# DT_AZP1524B1_SCH1_SHEET2__00A.net
KiCad netlist of a schematic drawn in Altium Designer
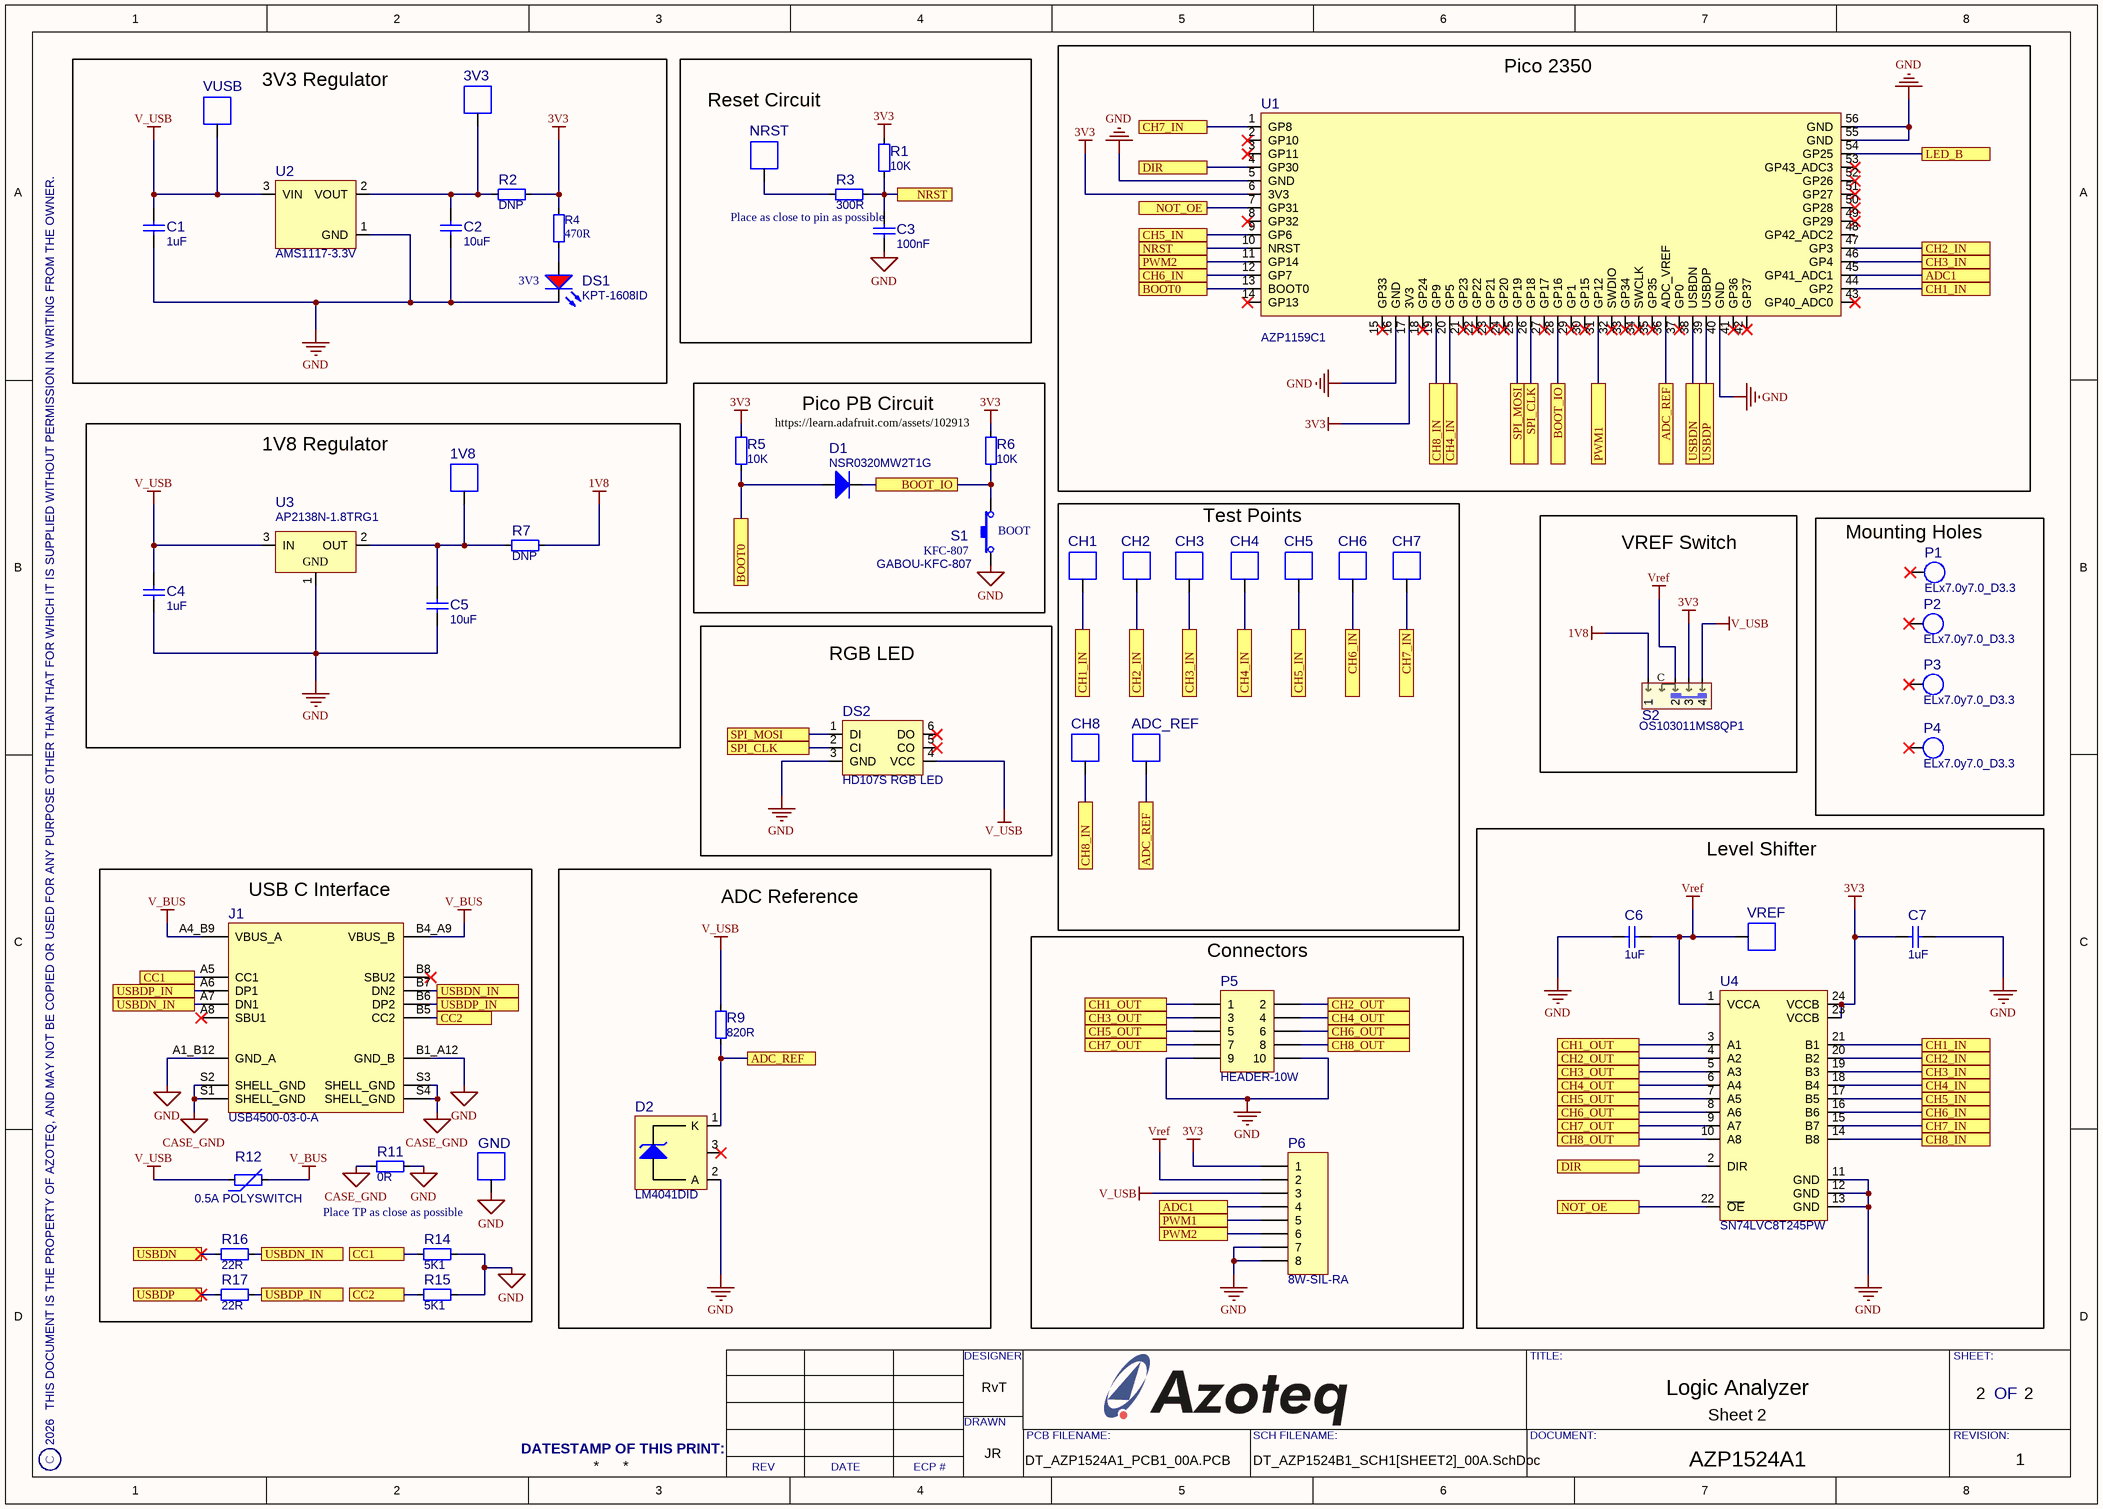
[diagram p0: DT_AZP1524B1_SCH1[SHEET2]_00A.SchDoc]

(export (version "E")
  (design (tool "Eeschema 10.0.6"))
  (components
    (comp (ref "1V8")
      (value "~")
      (footprint "TEST-POINT-1.5MM")
      (fields (field (name "CHECKED_BY") "*"))
      (libsource (lib "Miscellaneous") (part "TEST-POINT-SMD-1.5MM"))
    )
    (comp (ref "3V3")
      (value "~")
      (footprint "TEST-POINT-1.5MM")
      (fields (field (name "CHECKED_BY") "*"))
      (libsource (lib "Miscellaneous") (part "TEST-POINT-SMD-1.5MM"))
    )
    (comp (ref "ADC_REF")
      (value "~")
      (footprint "TEST-POINT-1.5MM")
      (fields (field (name "CHECKED_BY") "*"))
      (libsource (lib "Miscellaneous") (part "TEST-POINT-SMD-1.5MM"))
    )
    (comp (ref "C1")
      (value "1uF")
      (footprint "C-0603")
      (description "Capacitor, Ceramic, 1uF, 0603, X5R, 10%, 10V")
      (fields
        (field (name "INT_PART_NUMBER") "CAP0021")
        (field (name "MANUFACTURER") "Samsung")
        (field (name "CHECKED_BY") "Jason Reinecke")
      )
      (libsource (lib "Passive") (part "CAP 1u0F 0603 CER X5R 10% 10V"))
    )
    (comp (ref "C2")
      (value "10uF")
      (footprint "C-0603")
      (description "Capacitor, Ceramic, 10uF, 0603, X5R, 20%, 6V3 SAMSUNG")
      (fields
        (field (name "INT_PART_NUMBER") "CAP0076")
        (field (name "MANUFACTURER") "SAMSUNG")
        (field (name "CHECKED_BY") "Jason Reinecke")
      )
      (libsource (lib "Passive") (part "CAP 10uF 0603 CER X5R 20% 6V3 SAMSUNG"))
    )
    (comp (ref "C3")
      (value "100nF")
      (footprint "C-0603")
      (description "Capacitor, Ceramic, 100nF, 0603, X7R, 10%, 50V")
      (fields
        (field (name "INT_PART_NUMBER") "CAP0032")
        (field (name "MANUFACTURER") "Samsung")
        (field (name "CHECKED_BY") "Jason Reinecke")
      )
      (libsource (lib "Passive") (part "CAP 100nF 0603 CER X7R 10% 50V"))
    )
    (comp (ref "C4")
      (value "1uF")
      (footprint "C-0603")
      (description "Capacitor, Ceramic, 1uF, 0603, X5R, 10%, 10V")
      (fields
        (field (name "INT_PART_NUMBER") "CAP0021")
        (field (name "MANUFACTURER") "Samsung")
        (field (name "CHECKED_BY") "Jason Reinecke")
      )
      (libsource (lib "Passive") (part "CAP 1u0F 0603 CER X5R 10% 10V"))
    )
    (comp (ref "C5")
      (value "10uF")
      (footprint "C-0603")
      (description "Capacitor, Ceramic, 10uF, 0603, X5R, 20%, 6V3 SAMSUNG")
      (fields
        (field (name "INT_PART_NUMBER") "CAP0076")
        (field (name "MANUFACTURER") "SAMSUNG")
        (field (name "CHECKED_BY") "Jason Reinecke")
      )
      (libsource (lib "Passive") (part "CAP 10uF 0603 CER X5R 20% 6V3 SAMSUNG"))
    )
    (comp (ref "C6")
      (value "1uF")
      (footprint "C-0603")
      (description "Capacitor, Ceramic, 1uF, 0603, X5R, 10%, 10V")
      (fields
        (field (name "INT_PART_NUMBER") "CAP0021")
        (field (name "MANUFACTURER") "Samsung")
        (field (name "CHECKED_BY") "Jason Reinecke")
      )
      (libsource (lib "Passive") (part "CAP 1u0F 0603 CER X5R 10% 10V"))
    )
    (comp (ref "C7")
      (value "1uF")
      (footprint "C-0603")
      (description "Capacitor, Ceramic, 1uF, 0603, X5R, 10%, 10V")
      (fields
        (field (name "INT_PART_NUMBER") "CAP0021")
        (field (name "MANUFACTURER") "Samsung")
        (field (name "CHECKED_BY") "Jason Reinecke")
      )
      (libsource (lib "Passive") (part "CAP 1u0F 0603 CER X5R 10% 10V"))
    )
    (comp (ref "CH1")
      (value "~")
      (footprint "TEST-POINT-1.5MM")
      (fields (field (name "CHECKED_BY") "*"))
      (libsource (lib "Miscellaneous") (part "TEST-POINT-SMD-1.5MM"))
    )
    (comp (ref "CH2")
      (value "~")
      (footprint "TEST-POINT-1.5MM")
      (fields (field (name "CHECKED_BY") "*"))
      (libsource (lib "Miscellaneous") (part "TEST-POINT-SMD-1.5MM"))
    )
    (comp (ref "CH3")
      (value "~")
      (footprint "TEST-POINT-1.5MM")
      (fields (field (name "CHECKED_BY") "*"))
      (libsource (lib "Miscellaneous") (part "TEST-POINT-SMD-1.5MM"))
    )
    (comp (ref "CH4")
      (value "~")
      (footprint "TEST-POINT-1.5MM")
      (fields (field (name "CHECKED_BY") "*"))
      (libsource (lib "Miscellaneous") (part "TEST-POINT-SMD-1.5MM"))
    )
    (comp (ref "CH5")
      (value "~")
      (footprint "TEST-POINT-1.5MM")
      (fields (field (name "CHECKED_BY") "*"))
      (libsource (lib "Miscellaneous") (part "TEST-POINT-SMD-1.5MM"))
    )
    (comp (ref "CH6")
      (value "~")
      (footprint "TEST-POINT-1.5MM")
      (fields (field (name "CHECKED_BY") "*"))
      (libsource (lib "Miscellaneous") (part "TEST-POINT-SMD-1.5MM"))
    )
    (comp (ref "CH7")
      (value "~")
      (footprint "TEST-POINT-1.5MM")
      (fields (field (name "CHECKED_BY") "*"))
      (libsource (lib "Miscellaneous") (part "TEST-POINT-SMD-1.5MM"))
    )
    (comp (ref "CH8")
      (value "~")
      (footprint "TEST-POINT-1.5MM")
      (fields (field (name "CHECKED_BY") "*"))
      (libsource (lib "Miscellaneous") (part "TEST-POINT-SMD-1.5MM"))
    )
    (comp (ref "D1")
      (value "NSR0320MW2T1G")
      (footprint "D-SOD-323")
      (description "Diode Schottky 20V 1A 2-Pin SOD-323 T/R")
      (fields
        (field (name "INT_PART_NUMBER") "DIO0074")
        (field (name "MANUFACTURER") "ONsemiconductors")
        (field (name "CHECKED_BY") "*")
      )
      (libsource (lib "Discrete") (part "Diode Schottky 20V 1A SOD-323"))
    )
    (comp (ref "D2")
      (value "LM4041DID")
      (footprint "SOT-23")
      (fields (field (name "MANUFACTURER") "Texas Instruments") (field (name "CHECKED_BY") "*"))
      (libsource (lib "Discrete") (part "DIODE-ZENER-LM4041-SOT-23"))
    )
    (comp (ref "DS1")
      (value "KPT-1608ID")
      (footprint "D-LED-RED-0603")
      (fields (field (name "MANUFACTURER") "KingBright") (field (name "CHECKED_BY") "*"))
      (libsource (lib "Discrete") (part "LED-KPT1608ID-RED-0603"))
    )
    (comp (ref "DS2")
      (value "HD107S RGB LED")
      (footprint "CABA-CBT-5050GHRGB-16T")
      (description "LED, 5.5x5.0x1.6mm TOP SMD Type 0.2Watt")
      (fields
        (field (name "MANUFACTURER") "NEW STAR LED CO., LIMITED")
        (field (name "VOLTAGE") "5V")
        (field (name "CHECKED_BY") "*")
      )
      (libsource (lib "Discrete") (part "LED-NEWSTAR-HD107S RGB LED"))
    )
    (comp (ref "GND")
      (value "~")
      (footprint "TEST-POINT-1.5MM")
      (fields (field (name "CHECKED_BY") "*"))
      (libsource (lib "Miscellaneous") (part "TEST-POINT-SMD-1.5MM"))
    )
    (comp (ref "J1")
      (value "USB4500-03-0-A")
      (footprint "J-USB-GCT-USB4500-03-0-A")
      (description "USB-C TYPE REC 16P, 3U\" MID MNT 0.8MM USB2.0")
      (fields
        (field (name "INT_PART_NUMBER") "NONE")
        (field (name "MANUFACTURER") "GCT")
        (field (name "CHECKED_BY") "Jason Reinecke")
      )
      (libsource (lib "Connectors") (part "USB-GCT-USB4500-03-0-A"))
    )
    (comp (ref "NRST")
      (value "~")
      (footprint "TEST-POINT-1.5MM")
      (fields (field (name "CHECKED_BY") "*"))
      (libsource (lib "Miscellaneous") (part "TEST-POINT-SMD-1.5MM"))
    )
    (comp (ref "P1")
      (value "ELx7.0y7.0_D3.3")
      (footprint "MPAD-X7.0Y7.0_D3.3")
      (fields (field (name "CHECKED_BY") "*"))
      (libsource (lib "MPads") (part "MPAD-ELx7.0y7.0_D3.3"))
    )
    (comp (ref "P2")
      (value "ELx7.0y7.0_D3.3")
      (footprint "MPAD-X7.0Y7.0_D3.3")
      (fields (field (name "CHECKED_BY") "*"))
      (libsource (lib "MPads") (part "MPAD-ELx7.0y7.0_D3.3"))
    )
    (comp (ref "P3")
      (value "ELx7.0y7.0_D3.3")
      (footprint "MPAD-X7.0Y7.0_D3.3")
      (fields (field (name "CHECKED_BY") "*"))
      (libsource (lib "MPads") (part "MPAD-ELx7.0y7.0_D3.3"))
    )
    (comp (ref "P4")
      (value "ELx7.0y7.0_D3.3")
      (footprint "MPAD-X7.0Y7.0_D3.3")
      (fields (field (name "CHECKED_BY") "*"))
      (libsource (lib "MPads") (part "MPAD-ELx7.0y7.0_D3.3"))
    )
    (comp (ref "P5")
      (value "HEADER-10W")
      (footprint "P-BERG-10W-HDR-EDGE")
      (description "Connector, Header, Edge Mount,DIL, 10W, SMT")
      (fields (field (name "CHECKED_BY") "*"))
      (libsource (lib "Connectors") (part "BERG-10W-HDR-EDGE"))
    )
    (comp (ref "P6")
      (value "8W-SIL-RA")
      (footprint "P-BERG-8W-HDR-RA-SIL")
      (description "Connector, Header, Right angle, SIL, 8W, THP")
      (fields (field (name "MANUFACTURER") "Ho Chien"))
      (libsource (lib "Connectors") (part "BERG-8W-HDR-RA-SIL"))
    )
    (comp (ref "R1")
      (value "10K")
      (footprint "R-0603")
      (description "Resistor, 0603, 5%, 0.1W")
      (fields
        (field (name "INT_PART_NUMBER") "MNFR04")
        (field (name "TOLERANCE") "5%")
        (field (name "CHECKED_BY") "Jason Reinecke")
      )
      (libsource (lib "") (part "MNFR 0603 5% 0.1W_1"))
    )
    (comp (ref "R2")
      (value "DNP")
      (footprint "R-0603")
      (description "Resistor, DNP, 0603")
      (fields (field (name "CHECKED_BY") "Jason Reinecke"))
      (libsource (lib "Passive") (part "RES DNP 0603"))
    )
    (comp (ref "R3")
      (value "300R")
      (footprint "R-0603")
      (description "Resistor, 0603, 5%, 0.1W")
      (fields
        (field (name "INT_PART_NUMBER") "MNFR04")
        (field (name "TOLERANCE") "5%")
        (field (name "CHECKED_BY") "Jason Reinecke")
      )
      (libsource (lib "") (part "MNFR 0603 5% 0.1W_2"))
    )
    (comp (ref "R4")
      (value "470R")
      (footprint "R-0603")
      (description "Res Thick Film 0603 470 Ohm 5% 0.1W(1/10W) ±100ppm/°C Molded SMD Paper T/R")
      (fields
        (field (name "INT_PART_NUMBER") "RES0307")
        (field (name "MANUFACTURER") "Yageo")
        (field (name "CHECKED_BY") "Jason Reinecke")
      )
      (libsource (lib "Passive") (part "RES 470R 0603 5% 0.1W Yageo"))
    )
    (comp (ref "R5")
      (value "10K")
      (footprint "R-0603")
      (description "Resistor, 0603, 5%, 0.1W")
      (fields
        (field (name "INT_PART_NUMBER") "MNFR04")
        (field (name "TOLERANCE") "5%")
        (field (name "CHECKED_BY") "Jason Reinecke")
      )
      (libsource (lib "Passive") (part "MNFR 0603 5% 0.1W"))
    )
    (comp (ref "R6")
      (value "10K")
      (footprint "R-0603")
      (description "Resistor, 0603, 5%, 0.1W")
      (fields
        (field (name "INT_PART_NUMBER") "MNFR04")
        (field (name "TOLERANCE") "5%")
        (field (name "CHECKED_BY") "Jason Reinecke")
      )
      (libsource (lib "Passive") (part "MNFR 0603 5% 0.1W"))
    )
    (comp (ref "R7")
      (value "DNP")
      (footprint "R-0603")
      (description "Resistor, DNP, 0603")
      (fields (field (name "CHECKED_BY") "Jason Reinecke"))
      (libsource (lib "Passive") (part "RES DNP 0603"))
    )
    (comp (ref "R9")
      (value "820R")
      (footprint "R-0603")
      (description "Resistor, 820R, 0603, 1%, 0.1W")
      (fields (field (name "TOLERANCE") "1%") (field (name "CHECKED_BY") "Jason Reinecke"))
      (libsource (lib "Passive") (part "RES 820R 0603 1% 0.1W"))
    )
    (comp (ref "R11")
      (value "0R")
      (footprint "R-0603")
      (description "Res Thick Film 0603 0 Ohm Molded SMD Paper T/R")
      (fields
        (field (name "INT_PART_NUMBER") "RES0139")
        (field (name "MANUFACTURER") "Yageo")
        (field (name "CHECKED_BY") "Jason Reinecke")
      )
      (libsource (lib "Passive") (part "RES 0R 0603 1% 0.1W Yageo"))
    )
    (comp (ref "R12")
      (value "0.5A POLYSWITCH")
      (footprint "R-POLYSWITCH-1206")
      (description "Polyswitch, nanoSMDC050F, 1206, 0.5A, 13.2V")
      (fields
        (field (name "INT_PART_NUMBER") "SWT0070")
        (field (name "MANUFACTURER") "Tyco")
        (field (name "CHECKED_BY") "Jason Reinecke")
      )
      (libsource (lib "Passive") (part "POLYSWITCH-nanoSMDC050F/13.2"))
    )
    (comp (ref "R14")
      (value "5K1")
      (footprint "R-0603")
      (description "Resistor, 0603, 1%, 0.1W")
      (fields
        (field (name "INT_PART_NUMBER") "MNFR03")
        (field (name "TOLERANCE") "1%")
        (field (name "CHECKED_BY") "*")
      )
      (libsource (lib "Passive") (part "MNFR 0603 1% 0.1W"))
    )
    (comp (ref "R15")
      (value "5K1")
      (footprint "R-0603")
      (description "Resistor, 0603, 1%, 0.1W")
      (fields
        (field (name "INT_PART_NUMBER") "MNFR03")
        (field (name "TOLERANCE") "1%")
        (field (name "CHECKED_BY") "*")
      )
      (libsource (lib "Passive") (part "MNFR 0603 1% 0.1W"))
    )
    (comp (ref "R16")
      (value "22R")
      (footprint "R-0603")
      (description "Resistor, 0603, 1%, 0.1W")
      (fields
        (field (name "INT_PART_NUMBER") "MNFR03")
        (field (name "TOLERANCE") "1%")
        (field (name "CHECKED_BY") "*")
      )
      (libsource (lib "Passive") (part "MNFR 0603 1% 0.1W"))
    )
    (comp (ref "R17")
      (value "22R")
      (footprint "R-0603")
      (description "Resistor, 0603, 1%, 0.1W")
      (fields
        (field (name "INT_PART_NUMBER") "MNFR03")
        (field (name "TOLERANCE") "1%")
        (field (name "CHECKED_BY") "*")
      )
      (libsource (lib "") (part "MNFR 0603 1% 0.1W_1"))
    )
    (comp (ref "S1")
      (value "GABOU-KFC-807")
      (footprint "S-GABOU-KFC-807")
      (description "SWITCH TACTILE SPST-NO 0.05A 12V")
      (fields
        (field (name "MANUFACTURER") "GABOU")
        (field (name "VOLTAGE") "12V")
        (field (name "ALTIUM_VALUE") "KFC-807")
      )
      (libsource (lib "Switches") (part "GABOU-KFC-807"))
    )
    (comp (ref "S2")
      (value "OS103011MS8QP1")
      (footprint "S-C&K-OS103011MS8QP1")
      (description "SWITCH SLIDE SP3T 100MA 12V")
      (fields (field (name "MANUFACTURER") "C&K") (field (name "3D_PART") "No"))
      (libsource (lib "Switches") (part "C&K-OS103011MS8QP1"))
    )
    (comp (ref "U1")
      (value "AZP1159C1")
      (footprint "AZP1159C1")
      (description "AZP115C01: RP2350 Stamp (Pi Pico) - stamp breakout")
      (fields
        (field (name "INT_PART_NUMBER") "NONE")
        (field (name "MANUFACTURER") "Azoteq")
        (field (name "CHECKED_BY") "Jason Reinecke")
      )
      (libsource (lib "Hardware") (part "AZP1159C1"))
    )
    (comp (ref "U2")
      (value "AMS1117-3.3V")
      (footprint "SOT-223")
      (description "IC, Voltage Regulator, 3.3V Out, 4.7-18V In, 1A")
      (fields
        (field (name "INT_PART_NUMBER") "NONE")
        (field (name "MANUFACTURER") "MSKSEMI")
        (field (name "CHECKED_BY") "Jason Reinecke")
      )
      (libsource (lib "IC") (part "AMS1117-MSKSEMI-SOT-223"))
    )
    (comp (ref "U3")
      (value "AP2138N-1.8TRG1")
      (footprint "SOT-23")
      (description "IC REG LINEAR 1.8V 250MA SOT23-3")
      (fields
        (field (name "MANUFACTURER") "Diodes Incorporated")
        (field (name "VOLTAGE") "1.8V")
        (field (name "CHECKED_BY") "Jason Reinecke")
      )
      (libsource (lib "IC") (part "AP2138N-1.8TRG1-SOT-23"))
    )
    (comp (ref "U4")
      (value "SN74LVC8T245PW")
      (footprint "U-TSSOP-24")
      (fields (field (name "MANUFACTURER") "Texas Instruments") (field (name "CHECKED_BY") "*"))
      (libsource (lib "IC") (part "SN74LVC8T245PW-TSSOP-24"))
    )
    (comp (ref "VREF")
      (value "~")
      (footprint "TEST-POINT-1.5MM")
      (fields (field (name "CHECKED_BY") "*"))
      (libsource (lib "Miscellaneous") (part "TEST-POINT-SMD-1.5MM"))
    )
    (comp (ref "VUSB")
      (value "~")
      (footprint "TEST-POINT-1.5MM")
      (fields (field (name "CHECKED_BY") "*"))
      (libsource (lib "Miscellaneous") (part "TEST-POINT-SMD-1.5MM"))
    )
  )
  (nets
    (net (code "1") (name "/ADC1") (class "Default")
      (node (ref "P6") (pin "4") (pinfunction "4_4") (pintype "passive"))
      (node (ref "U1") (pin "45") (pinfunction "GP41_ADC1_45") (pintype "passive"))
    )
    (net (code "2") (name "/ADC_REF") (class "Default")
      (node (ref "ADC_REF") (pin "1") (pinfunction "1_1") (pintype "passive"))
      (node (ref "D2") (pin "1") (pinfunction "K_1") (pintype "passive"))
      (node (ref "R9") (pin "1") (pinfunction "1_1") (pintype "passive"))
      (node (ref "U1") (pin "36") (pinfunction "ADC_VREF_36") (pintype "passive"))
    )
    (net (code "3") (name "/BOOT0") (class "Default")
      (node (ref "D1") (pin "2") (pinfunction "K_2") (pintype "passive"))
      (node (ref "R5") (pin "2") (pinfunction "2_2") (pintype "passive"))
      (node (ref "U1") (pin "13") (pinfunction "BOOT0_13") (pintype "passive"))
    )
    (net (code "4") (name "/BOOT_IO") (class "Default")
      (node (ref "D1") (pin "1") (pinfunction "K_1") (pintype "passive"))
      (node (ref "R6") (pin "2") (pinfunction "2_2") (pintype "passive"))
      (node (ref "S1") (pin "2") (pinfunction "2_2") (pintype "passive"))
      (node (ref "U1") (pin "28") (pinfunction "GP16_28") (pintype "passive"))
    )
    (net (code "5") (name "/CC1") (class "Default")
      (node (ref "J1") (pin "A5") (pinfunction "CC1_A5") (pintype "passive"))
      (node (ref "R14") (pin "1") (pinfunction "1_1") (pintype "passive"))
    )
    (net (code "6") (name "/CC2") (class "Default")
      (node (ref "J1") (pin "B5") (pinfunction "CC2_B5") (pintype "passive"))
      (node (ref "R15") (pin "1") (pinfunction "1_1") (pintype "passive"))
    )
    (net (code "7") (name "/CH1_IN") (class "Default")
      (node (ref "CH1") (pin "1") (pinfunction "1_1") (pintype "passive"))
      (node (ref "U1") (pin "44") (pinfunction "GP2_44") (pintype "passive"))
      (node (ref "U4") (pin "21") (pinfunction "B1_21") (pintype "passive"))
    )
    (net (code "8") (name "/CH1_OUT") (class "Default")
      (node (ref "P5") (pin "1") (pinfunction "1_1") (pintype "passive"))
      (node (ref "U4") (pin "3") (pinfunction "A1_3") (pintype "passive"))
    )
    (net (code "9") (name "/CH2_IN") (class "Default")
      (node (ref "CH2") (pin "1") (pinfunction "1_1") (pintype "passive"))
      (node (ref "U1") (pin "47") (pinfunction "GP3_47") (pintype "passive"))
      (node (ref "U4") (pin "20") (pinfunction "B2_20") (pintype "passive"))
    )
    (net (code "10") (name "/CH2_OUT") (class "Default")
      (node (ref "P5") (pin "2") (pinfunction "2_2") (pintype "passive"))
      (node (ref "U4") (pin "4") (pinfunction "A2_4") (pintype "passive"))
    )
    (net (code "11") (name "/CH3_IN") (class "Default")
      (node (ref "CH3") (pin "1") (pinfunction "1_1") (pintype "passive"))
      (node (ref "U1") (pin "46") (pinfunction "GP4_46") (pintype "passive"))
      (node (ref "U4") (pin "19") (pinfunction "B3_19") (pintype "passive"))
    )
    (net (code "12") (name "/CH3_OUT") (class "Default")
      (node (ref "P5") (pin "3") (pinfunction "3_3") (pintype "passive"))
      (node (ref "U4") (pin "5") (pinfunction "A3_5") (pintype "passive"))
    )
    (net (code "13") (name "/CH4_IN") (class "Default")
      (node (ref "CH4") (pin "1") (pinfunction "1_1") (pintype "passive"))
      (node (ref "U1") (pin "20") (pinfunction "GP5_20") (pintype "passive"))
      (node (ref "U4") (pin "18") (pinfunction "B4_18") (pintype "passive"))
    )
    (net (code "14") (name "/CH4_OUT") (class "Default")
      (node (ref "P5") (pin "4") (pinfunction "4_4") (pintype "passive"))
      (node (ref "U4") (pin "6") (pinfunction "A4_6") (pintype "passive"))
    )
    (net (code "15") (name "/CH5_IN") (class "Default")
      (node (ref "CH5") (pin "1") (pinfunction "1_1") (pintype "passive"))
      (node (ref "U1") (pin "9") (pinfunction "GP6_9") (pintype "passive"))
      (node (ref "U4") (pin "17") (pinfunction "B5_17") (pintype "passive"))
    )
    (net (code "16") (name "/CH5_OUT") (class "Default")
      (node (ref "P5") (pin "5") (pinfunction "5_5") (pintype "passive"))
      (node (ref "U4") (pin "7") (pinfunction "A5_7") (pintype "passive"))
    )
    (net (code "17") (name "/CH6_IN") (class "Default")
      (node (ref "CH6") (pin "1") (pinfunction "1_1") (pintype "passive"))
      (node (ref "U1") (pin "12") (pinfunction "GP7_12") (pintype "passive"))
      (node (ref "U4") (pin "16") (pinfunction "B6_16") (pintype "passive"))
    )
    (net (code "18") (name "/CH6_OUT") (class "Default")
      (node (ref "P5") (pin "6") (pinfunction "6_6") (pintype "passive"))
      (node (ref "U4") (pin "8") (pinfunction "A6_8") (pintype "passive"))
    )
    (net (code "19") (name "/CH7_IN") (class "Default")
      (node (ref "CH7") (pin "1") (pinfunction "1_1") (pintype "passive"))
      (node (ref "U1") (pin "1") (pinfunction "GP8_1") (pintype "passive"))
      (node (ref "U4") (pin "15") (pinfunction "B7_15") (pintype "passive"))
    )
    (net (code "20") (name "/CH7_OUT") (class "Default")
      (node (ref "P5") (pin "7") (pinfunction "7_7") (pintype "passive"))
      (node (ref "U4") (pin "9") (pinfunction "A7_9") (pintype "passive"))
    )
    (net (code "21") (name "/CH8_IN") (class "Default")
      (node (ref "CH8") (pin "1") (pinfunction "1_1") (pintype "passive"))
      (node (ref "U1") (pin "19") (pinfunction "GP9_19") (pintype "passive"))
      (node (ref "U4") (pin "14") (pinfunction "B8_14") (pintype "passive"))
    )
    (net (code "22") (name "/CH8_OUT") (class "Default")
      (node (ref "P5") (pin "8") (pinfunction "8_8") (pintype "passive"))
      (node (ref "U4") (pin "10") (pinfunction "A8_10") (pintype "passive"))
    )
    (net (code "23") (name "/DIR") (class "Default")
      (node (ref "U1") (pin "4") (pinfunction "GP30_4") (pintype "passive"))
      (node (ref "U4") (pin "2") (pinfunction "DIR_2") (pintype "passive"))
    )
    (net (code "24") (name "/LED_B") (class "Default")
      (node (ref "U1") (pin "54") (pinfunction "GP25_54") (pintype "passive"))
    )
    (net (code "25") (name "/NOT_OE") (class "Default")
      (node (ref "U1") (pin "7") (pinfunction "GP31_7") (pintype "passive"))
      (node (ref "U4") (pin "22") (pinfunction "~{OE}_22") (pintype "passive"))
    )
    (net (code "26") (name "/NRST") (class "Default")
      (node (ref "C3") (pin "2") (pinfunction "2_2") (pintype "passive"))
      (node (ref "R1") (pin "1") (pinfunction "1_1") (pintype "passive"))
      (node (ref "R3") (pin "2") (pinfunction "2_2") (pintype "passive"))
      (node (ref "U1") (pin "10") (pinfunction "NRST_10") (pintype "passive"))
    )
    (net (code "27") (name "/PWM1") (class "Default")
      (node (ref "P6") (pin "5") (pinfunction "5_5") (pintype "passive"))
      (node (ref "U1") (pin "31") (pinfunction "GP12_31") (pintype "passive"))
    )
    (net (code "28") (name "/PWM2") (class "Default")
      (node (ref "P6") (pin "6") (pinfunction "6_6") (pintype "passive"))
      (node (ref "U1") (pin "11") (pinfunction "GP14_11") (pintype "passive"))
    )
    (net (code "29") (name "/SPI_CLK") (class "Default")
      (node (ref "DS2") (pin "2") (pinfunction "CI_2") (pintype "passive"))
      (node (ref "U1") (pin "26") (pinfunction "GP18_26") (pintype "passive"))
    )
    (net (code "30") (name "/SPI_MOSI") (class "Default")
      (node (ref "DS2") (pin "1") (pinfunction "DI_1") (pintype "passive"))
      (node (ref "U1") (pin "25") (pinfunction "GP19_25") (pintype "passive"))
    )
    (net (code "31") (name "/USBDN") (class "Default")
      (node (ref "R16") (pin "1") (pinfunction "1_1") (pintype "passive"))
      (node (ref "U1") (pin "38") (pinfunction "USBDN_38") (pintype "passive"))
    )
    (net (code "32") (name "/USBDN_IN") (class "Default")
      (node (ref "J1") (pin "A7") (pinfunction "DN1_A7") (pintype "passive"))
      (node (ref "J1") (pin "B7") (pinfunction "DN2_B7") (pintype "passive"))
      (node (ref "R16") (pin "2") (pinfunction "2_2") (pintype "passive"))
    )
    (net (code "33") (name "/USBDP") (class "Default")
      (node (ref "R17") (pin "2") (pinfunction "2_2") (pintype "passive"))
      (node (ref "U1") (pin "39") (pinfunction "USBDP_39") (pintype "passive"))
    )
    (net (code "34") (name "/USBDP_IN") (class "Default")
      (node (ref "J1") (pin "A6") (pinfunction "DP1_A6") (pintype "passive"))
      (node (ref "J1") (pin "B6") (pinfunction "DP2_B6") (pintype "passive"))
      (node (ref "R17") (pin "1") (pinfunction "1_1") (pintype "passive"))
    )
    (net (code "35") (name "1V8") (class "Default")
      (node (ref "R7") (pin "2") (pinfunction "2_2") (pintype "passive"))
      (node (ref "S2") (pin "1") (pinfunction "1_1") (pintype "passive"))
    )
    (net (code "36") (name "3V3") (class "Default")
      (node (ref "C7") (pin "2") (pinfunction "2_2") (pintype "passive"))
      (node (ref "P6") (pin "1") (pinfunction "1_1") (pintype "passive"))
      (node (ref "R1") (pin "2") (pinfunction "2_2") (pintype "passive"))
      (node (ref "R2") (pin "2") (pinfunction "2_2") (pintype "passive"))
      (node (ref "R4") (pin "2") (pinfunction "2_2") (pintype "passive"))
      (node (ref "R5") (pin "1") (pinfunction "1_1") (pintype "passive"))
      (node (ref "R6") (pin "1") (pinfunction "1_1") (pintype "passive"))
      (node (ref "S2") (pin "3") (pinfunction "3_3") (pintype "passive"))
      (node (ref "U1") (pin "17") (pinfunction "3V3_17") (pintype "passive"))
      (node (ref "U1") (pin "6") (pinfunction "3V3_6") (pintype "passive"))
      (node (ref "U4") (pin "23") (pinfunction "VCCB_23") (pintype "passive"))
      (node (ref "U4") (pin "24") (pinfunction "VCCB_24") (pintype "passive"))
    )
    (net (code "37") (name "CASE_GND") (class "Default")
      (node (ref "J1") (pin "S1") (pinfunction "SHELL_GND_S1") (pintype "passive"))
      (node (ref "J1") (pin "S2") (pinfunction "SHELL_GND_S2") (pintype "passive"))
      (node (ref "J1") (pin "S3") (pinfunction "SHELL_GND_S3") (pintype "passive"))
      (node (ref "J1") (pin "S4") (pinfunction "SHELL_GND_S4") (pintype "passive"))
      (node (ref "R11") (pin "1") (pinfunction "1_1") (pintype "passive"))
    )
    (net (code "38") (name "GND") (class "Default")
      (node (ref "C1") (pin "1") (pinfunction "1_1") (pintype "passive"))
      (node (ref "C2") (pin "1") (pinfunction "1_1") (pintype "passive"))
      (node (ref "C3") (pin "1") (pinfunction "1_1") (pintype "passive"))
      (node (ref "C4") (pin "1") (pinfunction "1_1") (pintype "passive"))
      (node (ref "C5") (pin "1") (pinfunction "1_1") (pintype "passive"))
      (node (ref "C6") (pin "2") (pinfunction "2_2") (pintype "passive"))
      (node (ref "C7") (pin "1") (pinfunction "1_1") (pintype "passive"))
      (node (ref "D2") (pin "2") (pinfunction "A_2") (pintype "passive"))
      (node (ref "DS1") (pin "1") (pinfunction "K_1") (pintype "passive"))
      (node (ref "DS2") (pin "3") (pinfunction "GND_3") (pintype "passive"))
      (node (ref "GND") (pin "1") (pinfunction "1_1") (pintype "passive"))
      (node (ref "J1") (pin "A1_B12") (pinfunction "GND_A_A1_B12") (pintype "passive"))
      (node (ref "J1") (pin "B1_A12") (pinfunction "GND_B_B1_A12") (pintype "passive"))
      (node (ref "P5") (pin "10") (pinfunction "10_10") (pintype "passive"))
      (node (ref "P5") (pin "9") (pinfunction "9_9") (pintype "passive"))
      (node (ref "P6") (pin "7") (pinfunction "7_7") (pintype "passive"))
      (node (ref "P6") (pin "8") (pinfunction "8_8") (pintype "passive"))
      (node (ref "R11") (pin "2") (pinfunction "2_2") (pintype "passive"))
      (node (ref "R14") (pin "2") (pinfunction "2_2") (pintype "passive"))
      (node (ref "R15") (pin "2") (pinfunction "2_2") (pintype "passive"))
      (node (ref "S1") (pin "1") (pinfunction "1_1") (pintype "passive"))
      (node (ref "U1") (pin "16") (pinfunction "GND_16") (pintype "passive"))
      (node (ref "U1") (pin "40") (pinfunction "GND_40") (pintype "passive"))
      (node (ref "U1") (pin "5") (pinfunction "GND_5") (pintype "passive"))
      (node (ref "U1") (pin "55") (pinfunction "GND_55") (pintype "passive"))
      (node (ref "U1") (pin "56") (pinfunction "GND_56") (pintype "passive"))
      (node (ref "U2") (pin "1") (pinfunction "GND_1") (pintype "passive"))
      (node (ref "U3") (pin "1") (pinfunction "GND_1") (pintype "passive"))
      (node (ref "U4") (pin "11") (pinfunction "GND_11") (pintype "passive"))
      (node (ref "U4") (pin "12") (pinfunction "GND_12") (pintype "passive"))
      (node (ref "U4") (pin "13") (pinfunction "GND_13") (pintype "passive"))
    )
    (net (code "39") (name "Net-(DS1-A)") (class "Default")
      (node (ref "DS1") (pin "2") (pinfunction "A_2") (pintype "passive"))
      (node (ref "R4") (pin "1") (pinfunction "1_1") (pintype "passive"))
    )
    (net (code "40") (name "Net-(NRST-Pad1)") (class "Default")
      (node (ref "NRST") (pin "1") (pinfunction "1_1") (pintype "passive"))
      (node (ref "R3") (pin "1") (pinfunction "1_1") (pintype "passive"))
    )
    (net (code "41") (name "Net-(U2-VOUT)") (class "Default")
      (node (ref "3V3") (pin "1") (pinfunction "1_1") (pintype "passive"))
      (node (ref "C2") (pin "2") (pinfunction "2_2") (pintype "passive"))
      (node (ref "R2") (pin "1") (pinfunction "1_1") (pintype "passive"))
      (node (ref "U2") (pin "2") (pinfunction "VOUT_2") (pintype "passive"))
    )
    (net (code "42") (name "Net-(U3-OUT)") (class "Default")
      (node (ref "1V8") (pin "1") (pinfunction "1_1") (pintype "passive"))
      (node (ref "C5") (pin "2") (pinfunction "2_2") (pintype "passive"))
      (node (ref "R7") (pin "1") (pinfunction "1_1") (pintype "passive"))
      (node (ref "U3") (pin "2") (pinfunction "OUT_2") (pintype "passive"))
    )
    (net (code "43") (name "V_BUS") (class "Default")
      (node (ref "J1") (pin "A4_B9") (pinfunction "VBUS_A_A4_B9") (pintype "passive"))
      (node (ref "J1") (pin "B4_A9") (pinfunction "VBUS_B_B4_A9") (pintype "passive"))
      (node (ref "R12") (pin "2") (pinfunction "2_2") (pintype "passive"))
    )
    (net (code "44") (name "V_USB") (class "Default")
      (node (ref "C1") (pin "2") (pinfunction "2_2") (pintype "passive"))
      (node (ref "C4") (pin "2") (pinfunction "2_2") (pintype "passive"))
      (node (ref "DS2") (pin "4") (pinfunction "VCC_4") (pintype "passive"))
      (node (ref "P6") (pin "3") (pinfunction "3_3") (pintype "passive"))
      (node (ref "R12") (pin "1") (pinfunction "1_1") (pintype "passive"))
      (node (ref "R9") (pin "2") (pinfunction "2_2") (pintype "passive"))
      (node (ref "S2") (pin "4") (pinfunction "4_4") (pintype "passive"))
      (node (ref "U2") (pin "3") (pinfunction "VIN_3") (pintype "passive"))
      (node (ref "U3") (pin "3") (pinfunction "IN_3") (pintype "passive"))
      (node (ref "VUSB") (pin "1") (pinfunction "1_1") (pintype "passive"))
    )
    (net (code "45") (name "Vref") (class "Default")
      (node (ref "C6") (pin "1") (pinfunction "1_1") (pintype "passive"))
      (node (ref "P6") (pin "2") (pinfunction "2_2") (pintype "passive"))
      (node (ref "S2") (pin "2") (pinfunction "2_2") (pintype "passive"))
      (node (ref "U4") (pin "1") (pinfunction "VCCA_1") (pintype "passive"))
      (node (ref "VREF") (pin "1") (pinfunction "1_1") (pintype "passive"))
    )
    (net (code "46") (name "unconnected-(D2-Pad3)") (class "Default")
      (node (ref "D2") (pin "3") (pintype "passive+no_connect"))
    )
    (net (code "47") (name "unconnected-(DS2-CO-Pad5)") (class "Default")
      (node (ref "DS2") (pin "5") (pinfunction "CO_5") (pintype "passive+no_connect"))
    )
    (net (code "48") (name "unconnected-(DS2-DO-Pad6)") (class "Default")
      (node (ref "DS2") (pin "6") (pinfunction "DO_6") (pintype "passive+no_connect"))
    )
    (net (code "49") (name "unconnected-(J1-SBU1-PadA8)") (class "Default")
      (node (ref "J1") (pin "A8") (pinfunction "SBU1_A8") (pintype "passive+no_connect"))
    )
    (net (code "50") (name "unconnected-(J1-SBU2-PadB8)") (class "Default")
      (node (ref "J1") (pin "B8") (pinfunction "SBU2_B8") (pintype "passive+no_connect"))
    )
    (net (code "51") (name "unconnected-(P1-Pad1)") (class "Default")
      (node (ref "P1") (pin "1") (pintype "passive+no_connect"))
    )
    (net (code "52") (name "unconnected-(P2-Pad1)") (class "Default")
      (node (ref "P2") (pin "1") (pintype "passive+no_connect"))
    )
    (net (code "53") (name "unconnected-(P3-Pad1)") (class "Default")
      (node (ref "P3") (pin "1") (pintype "passive+no_connect"))
    )
    (net (code "54") (name "unconnected-(P4-Pad1)") (class "Default")
      (node (ref "P4") (pin "1") (pintype "passive+no_connect"))
    )
    (net (code "55") (name "unconnected-(U1-GP0-Pad37)") (class "Default")
      (node (ref "U1") (pin "37") (pinfunction "GP0_37") (pintype "passive+no_connect"))
    )
    (net (code "56") (name "unconnected-(U1-GP1-Pad29)") (class "Default")
      (node (ref "U1") (pin "29") (pinfunction "GP1_29") (pintype "passive+no_connect"))
    )
    (net (code "57") (name "unconnected-(U1-GP10-Pad2)") (class "Default")
      (node (ref "U1") (pin "2") (pinfunction "GP10_2") (pintype "passive+no_connect"))
    )
    (net (code "58") (name "unconnected-(U1-GP11-Pad3)") (class "Default")
      (node (ref "U1") (pin "3") (pinfunction "GP11_3") (pintype "passive+no_connect"))
    )
    (net (code "59") (name "unconnected-(U1-GP13-Pad14)") (class "Default")
      (node (ref "U1") (pin "14") (pinfunction "GP13_14") (pintype "passive+no_connect"))
    )
    (net (code "60") (name "unconnected-(U1-GP15-Pad30)") (class "Default")
      (node (ref "U1") (pin "30") (pinfunction "GP15_30") (pintype "passive+no_connect"))
    )
    (net (code "61") (name "unconnected-(U1-GP17-Pad27)") (class "Default")
      (node (ref "U1") (pin "27") (pinfunction "GP17_27") (pintype "passive+no_connect"))
    )
    (net (code "62") (name "unconnected-(U1-GP20-Pad24)") (class "Default")
      (node (ref "U1") (pin "24") (pinfunction "GP20_24") (pintype "passive+no_connect"))
    )
    (net (code "63") (name "unconnected-(U1-GP21-Pad23)") (class "Default")
      (node (ref "U1") (pin "23") (pinfunction "GP21_23") (pintype "passive+no_connect"))
    )
    (net (code "64") (name "unconnected-(U1-GP22-Pad22)") (class "Default")
      (node (ref "U1") (pin "22") (pinfunction "GP22_22") (pintype "passive+no_connect"))
    )
    (net (code "65") (name "unconnected-(U1-GP23-Pad21)") (class "Default")
      (node (ref "U1") (pin "21") (pinfunction "GP23_21") (pintype "passive+no_connect"))
    )
    (net (code "66") (name "unconnected-(U1-GP24-Pad18)") (class "Default")
      (node (ref "U1") (pin "18") (pinfunction "GP24_18") (pintype "passive+no_connect"))
    )
    (net (code "67") (name "unconnected-(U1-GP26-Pad52)") (class "Default")
      (node (ref "U1") (pin "52") (pinfunction "GP26_52") (pintype "passive+no_connect"))
    )
    (net (code "68") (name "unconnected-(U1-GP27-Pad51)") (class "Default")
      (node (ref "U1") (pin "51") (pinfunction "GP27_51") (pintype "passive+no_connect"))
    )
    (net (code "69") (name "unconnected-(U1-GP28-Pad50)") (class "Default")
      (node (ref "U1") (pin "50") (pinfunction "GP28_50") (pintype "passive+no_connect"))
    )
    (net (code "70") (name "unconnected-(U1-GP29-Pad49)") (class "Default")
      (node (ref "U1") (pin "49") (pinfunction "GP29_49") (pintype "passive+no_connect"))
    )
    (net (code "71") (name "unconnected-(U1-GP32-Pad8)") (class "Default")
      (node (ref "U1") (pin "8") (pinfunction "GP32_8") (pintype "passive+no_connect"))
    )
    (net (code "72") (name "unconnected-(U1-GP33-Pad15)") (class "Default")
      (node (ref "U1") (pin "15") (pinfunction "GP33_15") (pintype "passive+no_connect"))
    )
    (net (code "73") (name "unconnected-(U1-GP34-Pad33)") (class "Default")
      (node (ref "U1") (pin "33") (pinfunction "GP34_33") (pintype "passive+no_connect"))
    )
    (net (code "74") (name "unconnected-(U1-GP35-Pad35)") (class "Default")
      (node (ref "U1") (pin "35") (pinfunction "GP35_35") (pintype "passive+no_connect"))
    )
    (net (code "75") (name "unconnected-(U1-GP36-Pad41)") (class "Default")
      (node (ref "U1") (pin "41") (pinfunction "GP36_41") (pintype "passive+no_connect"))
    )
    (net (code "76") (name "unconnected-(U1-GP37-Pad42)") (class "Default")
      (node (ref "U1") (pin "42") (pinfunction "GP37_42") (pintype "passive+no_connect"))
    )
    (net (code "77") (name "unconnected-(U1-GP40_ADC0-Pad43)") (class "Default")
      (node (ref "U1") (pin "43") (pinfunction "GP40_ADC0_43") (pintype "passive+no_connect"))
    )
    (net (code "78") (name "unconnected-(U1-GP42_ADC2-Pad48)") (class "Default")
      (node (ref "U1") (pin "48") (pinfunction "GP42_ADC2_48") (pintype "passive"))
    )
    (net (code "79") (name "unconnected-(U1-GP43_ADC3-Pad53)") (class "Default")
      (node (ref "U1") (pin "53") (pinfunction "GP43_ADC3_53") (pintype "passive+no_connect"))
    )
    (net (code "80") (name "unconnected-(U1-SWCLK-Pad34)") (class "Default")
      (node (ref "U1") (pin "34") (pinfunction "SWCLK_34") (pintype "passive+no_connect"))
    )
    (net (code "81") (name "unconnected-(U1-SWDIO-Pad32)") (class "Default")
      (node (ref "U1") (pin "32") (pinfunction "SWDIO_32") (pintype "passive+no_connect"))
    )
  )
)
